# Warning_Light.net
KiCad netlist of a schematic drawn in Altium Designer
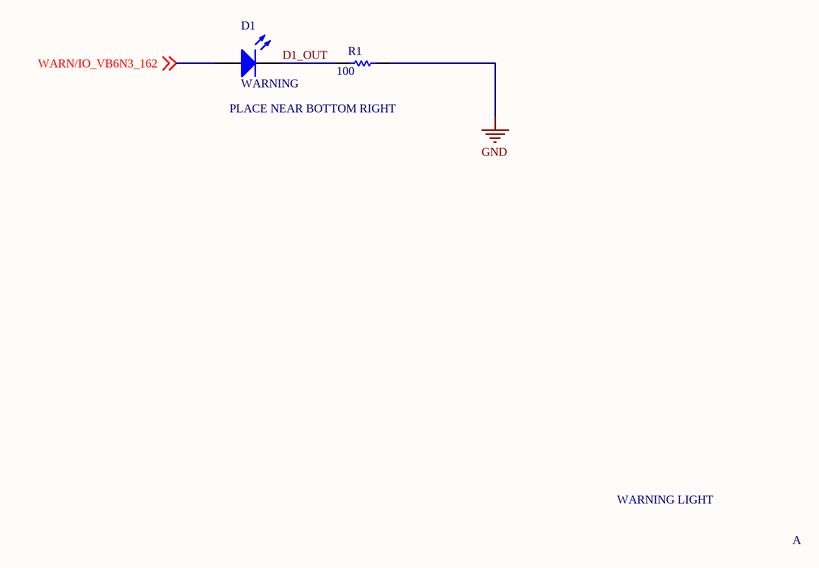
[diagram p0: Warning_Light.SchDoc]

(export (version "E")
  (design (tool "Eeschema 10.0.6"))
  (components
    (comp (ref "D1")
      (value "WARNING")
      (footprint "DIODE_0603")
      (description "Typical INFRARED GaAs LED")
      (fields (field (name "PUBLISHER") "Altium Limited"))
      (libsource (lib "Miscellaneous Devices") (part "LED0"))
    )
    (comp (ref "R1")
      (value "100")
      (footprint "RES_0603")
      (description "Resistor")
      (fields
        (field (name "Comment") "Figure out ohmage after RevA")
        (field (name "PUBLISHER") "Altium Limited")
      )
      (libsource (lib "Miscellaneous Devices") (part "Res1"))
    )
  )
  (nets
    (net (code "1") (name "/D1_OUT") (class "Default")
      (node (ref "D1") (pin "2") (pinfunction "K_2") (pintype "passive"))
      (node (ref "R1") (pin "1") (pinfunction "1_1") (pintype "passive"))
    )
    (net (code "2") (name "GND") (class "Default")
      (node (ref "R1") (pin "2") (pinfunction "2_2") (pintype "passive"))
    )
    (net (code "3") (name "WARN{slash}IO_VB6N3_162") (class "Default")
      (node (ref "D1") (pin "1") (pinfunction "A_1") (pintype "passive"))
    )
  )
)
